# Atomic_clock_test_board_v1_1.net
KiCad netlist of a schematic drawn in EAGLE
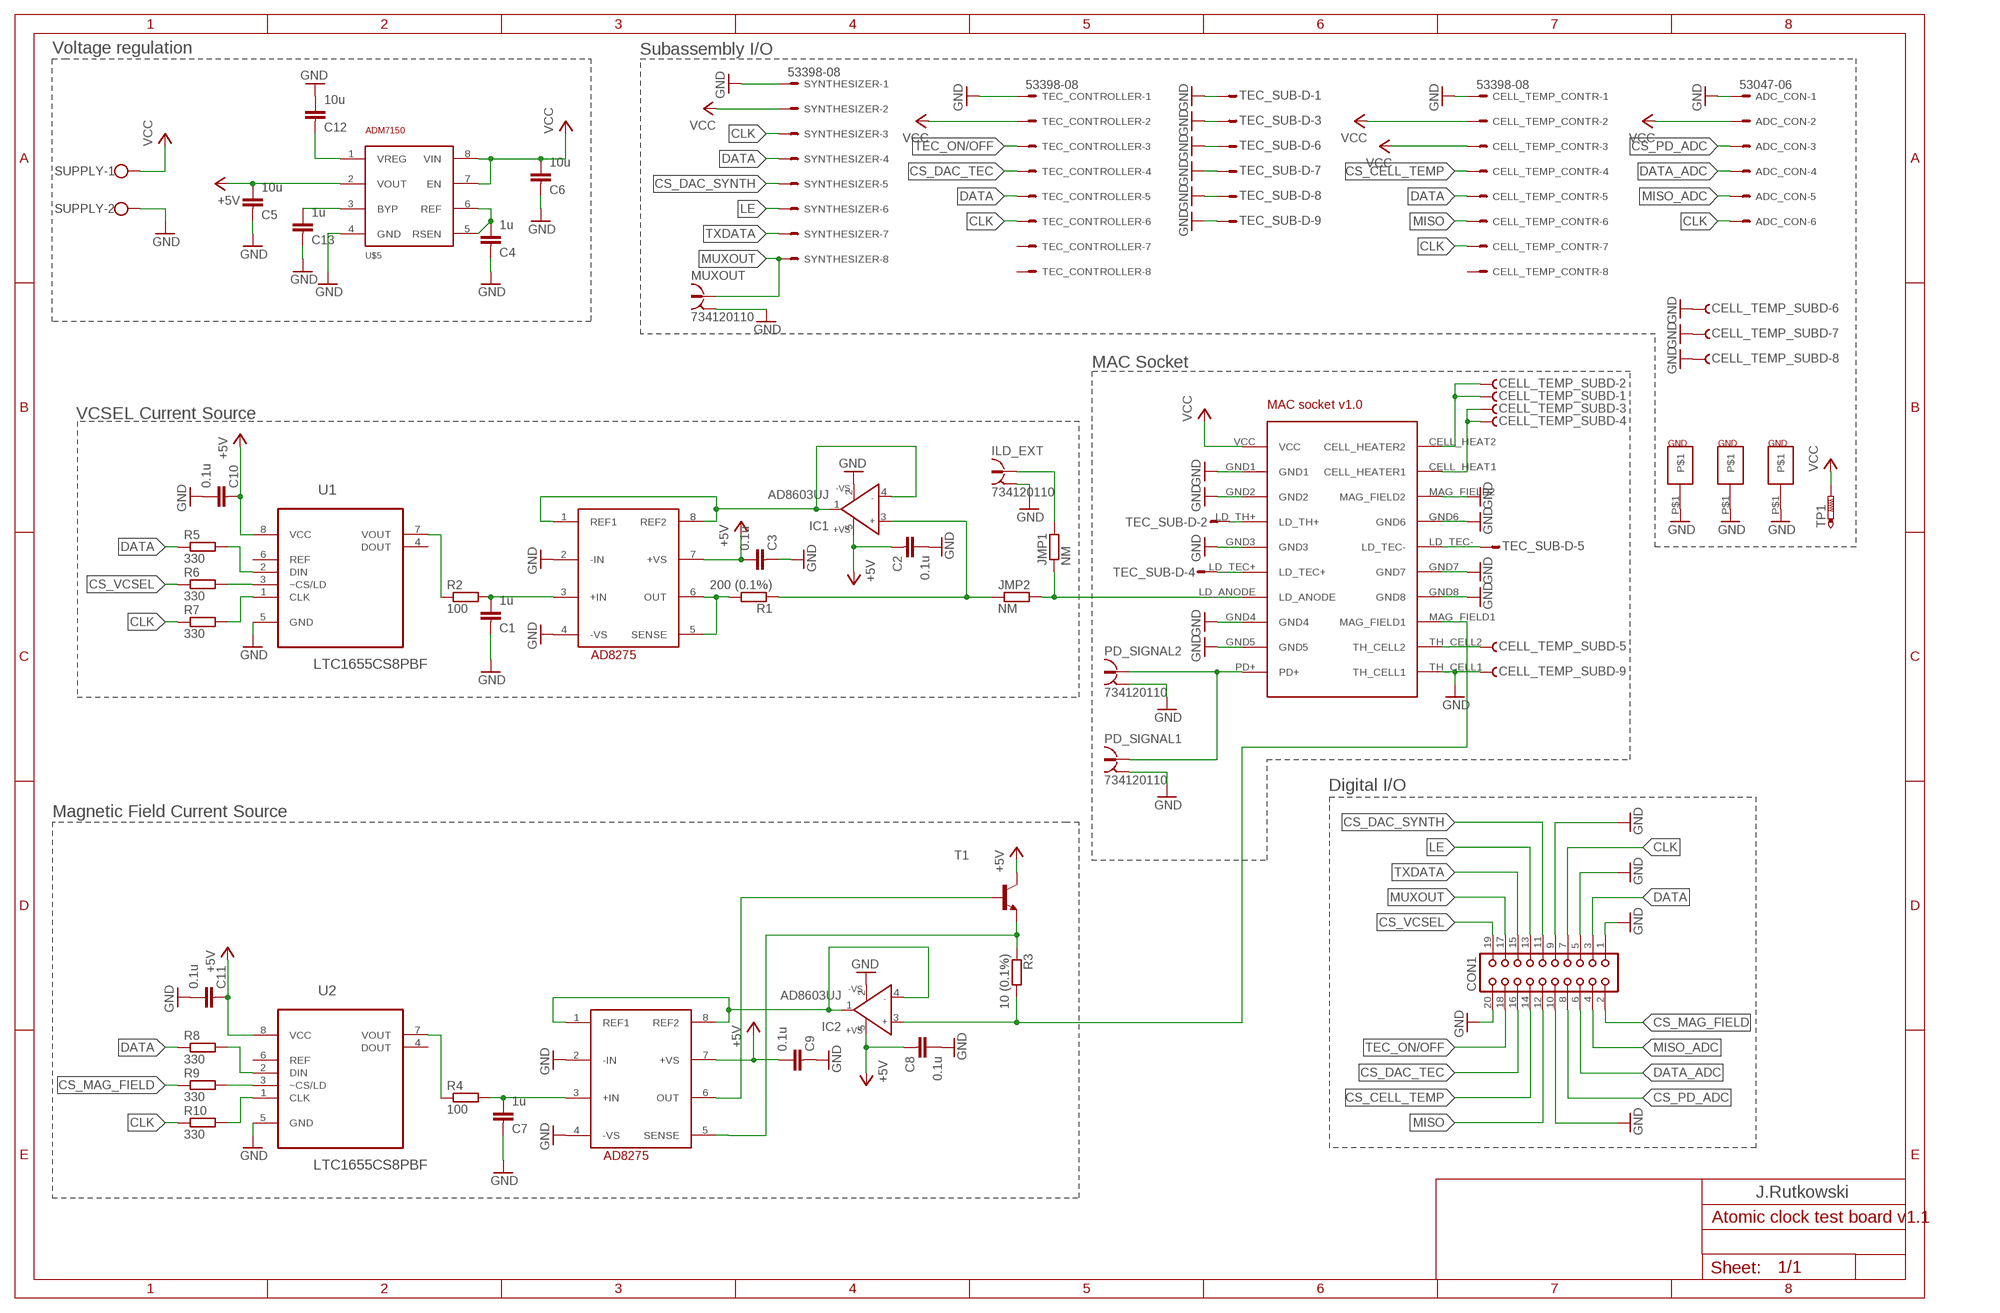
[diagram p0: schematic, sheet 1]

(export (version "E")
  (design (tool "Eeschema 10.0.6"))
  (components
    (comp (ref "ADC_CON")
      (value "53047-06")
      (footprint "eagle-import:53047-06")
      (fields (field (name "MPN") "53047-0610-C"))
      (libsource (lib "eagle-import") (part "53?-06047"))
    )
    (comp (ref "C1")
      (value "1u")
      (footprint "eagle-import:C0603K")
      (libsource (lib "eagle-import") (part "C-EUC0603K"))
    )
    (comp (ref "C2")
      (value "0.1u")
      (footprint "eagle-import:C0603K")
      (libsource (lib "eagle-import") (part "C-EUC0603K"))
    )
    (comp (ref "C3")
      (value "0.1u")
      (footprint "eagle-import:C0603K")
      (libsource (lib "eagle-import") (part "C-EUC0603K"))
    )
    (comp (ref "C4")
      (value "1u")
      (footprint "eagle-import:C0603K")
      (libsource (lib "eagle-import") (part "C-EUC0603K"))
    )
    (comp (ref "C5")
      (value "10u")
      (footprint "eagle-import:C0603K")
      (libsource (lib "eagle-import") (part "C-EUC0603K"))
    )
    (comp (ref "C6")
      (value "10u")
      (footprint "eagle-import:C0603K")
      (libsource (lib "eagle-import") (part "C-EUC0603K"))
    )
    (comp (ref "C7")
      (value "1u")
      (footprint "eagle-import:C0603K")
      (libsource (lib "eagle-import") (part "C-EUC0603K"))
    )
    (comp (ref "C8")
      (value "0.1u")
      (footprint "eagle-import:C0603K")
      (libsource (lib "eagle-import") (part "C-EUC0603K"))
    )
    (comp (ref "C9")
      (value "0.1u")
      (footprint "eagle-import:C0603K")
      (libsource (lib "eagle-import") (part "C-EUC0603K"))
    )
    (comp (ref "C10")
      (value "0.1u")
      (footprint "eagle-import:C0603K")
      (libsource (lib "eagle-import") (part "C-EUC0603K"))
    )
    (comp (ref "C11")
      (value "0.1u")
      (footprint "eagle-import:C0603K")
      (libsource (lib "eagle-import") (part "C-EUC0603K"))
    )
    (comp (ref "C12")
      (value "10u")
      (footprint "eagle-import:C0603K")
      (libsource (lib "eagle-import") (part "C-EUC0603K"))
    )
    (comp (ref "C13")
      (value "1u")
      (footprint "eagle-import:C0603K")
      (libsource (lib "eagle-import") (part "C-EUC0603K"))
    )
    (comp (ref "CELL_TEMP_CONTR")
      (value "53398-08")
      (footprint "eagle-import:53398-08")
      (libsource (lib "eagle-import") (part "53?-08398"))
    )
    (comp (ref "CELL_TEMP_SUBD")
      (value "F09HPS")
      (footprint "eagle-import:F09HP")
      (libsource (lib "eagle-import") (part "F09?SHP"))
    )
    (comp (ref "CON1")
      (value "CON20")
      (footprint "eagle-import:CON20")
      (libsource (lib "eagle-import") (part "CON20"))
    )
    (comp (ref "IC1")
      (value "AD8603UJ")
      (footprint "eagle-import:SOT23-5")
      (fields (field (name "MF") "ALTERA CORPORATION") (field (name "MPN") "AD8603AUJZ-REEL7"))
      (libsource (lib "eagle-import") (part "AD8603UJ"))
    )
    (comp (ref "IC2")
      (value "AD8603UJ")
      (footprint "eagle-import:SOT23-5")
      (fields (field (name "MF") "ALTERA CORPORATION") (field (name "MPN") "AD8603AUJZ-REEL7"))
      (libsource (lib "eagle-import") (part "AD8603UJ"))
    )
    (comp (ref "ILD_EXT")
      (value "734120110")
      (footprint "eagle-import:734120110")
      (libsource (lib "eagle-import") (part "734120110"))
    )
    (comp (ref "JMP1")
      (value "NM")
      (footprint "eagle-import:R0402")
      (libsource (lib "eagle-import") (part "R-EU_R0402"))
    )
    (comp (ref "JMP2")
      (value "NM")
      (footprint "eagle-import:R0402")
      (libsource (lib "eagle-import") (part "R-EU_R0402"))
    )
    (comp (ref "MUXOUT")
      (value "734120110")
      (footprint "eagle-import:734120110")
      (libsource (lib "eagle-import") (part "734120110"))
    )
    (comp (ref "PD_SIGNAL1")
      (value "734120110")
      (footprint "eagle-import:734120110")
      (libsource (lib "eagle-import") (part "734120110"))
    )
    (comp (ref "PD_SIGNAL2")
      (value "734120110")
      (footprint "eagle-import:734120110")
      (libsource (lib "eagle-import") (part "734120110"))
    )
    (comp (ref "R1")
      (value "200 (0.1%)")
      (footprint "eagle-import:R0603")
      (libsource (lib "eagle-import") (part "R-EU_R0603"))
    )
    (comp (ref "R2")
      (value "100")
      (footprint "eagle-import:R0603")
      (libsource (lib "eagle-import") (part "R-EU_R0603"))
    )
    (comp (ref "R3")
      (value "10 (0.1%)")
      (footprint "eagle-import:R0603")
      (libsource (lib "eagle-import") (part "R-EU_R0603"))
    )
    (comp (ref "R4")
      (value "100")
      (footprint "eagle-import:R0603")
      (libsource (lib "eagle-import") (part "R-EU_R0603"))
    )
    (comp (ref "R5")
      (value "330")
      (footprint "eagle-import:R0603")
      (libsource (lib "eagle-import") (part "R-EU_R0603"))
    )
    (comp (ref "R6")
      (value "330")
      (footprint "eagle-import:R0603")
      (libsource (lib "eagle-import") (part "R-EU_R0603"))
    )
    (comp (ref "R7")
      (value "330")
      (footprint "eagle-import:R0603")
      (libsource (lib "eagle-import") (part "R-EU_R0603"))
    )
    (comp (ref "R8")
      (value "330")
      (footprint "eagle-import:R0603")
      (libsource (lib "eagle-import") (part "R-EU_R0603"))
    )
    (comp (ref "R9")
      (value "330")
      (footprint "eagle-import:R0603")
      (libsource (lib "eagle-import") (part "R-EU_R0603"))
    )
    (comp (ref "R10")
      (value "330")
      (footprint "eagle-import:R0603")
      (libsource (lib "eagle-import") (part "R-EU_R0603"))
    )
    (comp (ref "SUPPLY")
      (value "W237-102")
      (footprint "eagle-import:W237-102")
      (fields (field (name "MPN") "237-102"))
      (libsource (lib "eagle-import") (part "W237-102"))
    )
    (comp (ref "SYNTHESIZER")
      (value "53398-08")
      (footprint "eagle-import:53398-08")
      (libsource (lib "eagle-import") (part "53?-08398"))
    )
    (comp (ref "T1")
      (value "MMBT3904LT1-NPN-SOT23-BEC")
      (footprint "eagle-import:SOT23-BEC")
      (libsource (lib "eagle-import") (part "-NPN-SOT23-BECMMBT3904LT1"))
    )
    (comp (ref "TEC_CONTROLLER")
      (value "53398-08")
      (footprint "eagle-import:53398-08")
      (libsource (lib "eagle-import") (part "53?-08398"))
    )
    (comp (ref "TEC_SUB-D")
      (value "M09HPS")
      (footprint "eagle-import:M09HP")
      (libsource (lib "eagle-import") (part "M09?SHP"))
    )
    (comp (ref "TP1")
      (value "PTR1PAD1-13")
      (footprint "eagle-import:P1-13")
      (libsource (lib "eagle-import") (part "PTR1PAD1-13"))
    )
    (comp (ref "U$1")
      (value "MAC_MOUNT_V1")
      (footprint "eagle-import:MAC_MOUNT_PAC_V1")
      (libsource (lib "eagle-import") (part "MAC_MOUNT_V1"))
    )
    (comp (ref "U$2")
      (value "AD8275")
      (footprint "eagle-import:MSOP08")
      (libsource (lib "eagle-import") (part "AD8275"))
    )
    (comp (ref "U$4")
      (value "AD8275")
      (footprint "eagle-import:MSOP08")
      (libsource (lib "eagle-import") (part "AD8275"))
    )
    (comp (ref "U$5")
      (value "ADM7150")
      (footprint "eagle-import:SO8")
      (libsource (lib "eagle-import") (part "ADM7150"))
    )
    (comp (ref "U$6")
      (value "GND_PAD")
      (footprint "eagle-import:GND_PAD")
      (libsource (lib "eagle-import") (part "GND_PAD"))
    )
    (comp (ref "U$7")
      (value "GND_PAD")
      (footprint "eagle-import:GND_PAD")
      (libsource (lib "eagle-import") (part "GND_PAD"))
    )
    (comp (ref "U$8")
      (value "GND_PAD")
      (footprint "eagle-import:GND_PAD")
      (libsource (lib "eagle-import") (part "GND_PAD"))
    )
    (comp (ref "U1")
      (value "LTC1655CS8PBF")
      (footprint "eagle-import:SOIC127P600X175-8N")
      (fields (field (name "MPN") "LTC1655CS8#PBF"))
      (libsource (lib "eagle-import") (part "LTC1655CS8PBF"))
    )
    (comp (ref "U2")
      (value "LTC1655CS8PBF")
      (footprint "eagle-import:SOIC127P600X175-8N")
      (fields (field (name "MPN") "LTC1655CS8#PBF"))
      (libsource (lib "eagle-import") (part "LTC1655CS8PBF"))
    )
  )
  (nets
    (net (code "1") (name "+5V") (class "Default")
      (node (ref "C10") (pin "2") (pinfunction "2_2") (pintype "passive"))
      (node (ref "C11") (pin "2") (pinfunction "2_2") (pintype "passive"))
      (node (ref "C2") (pin "2") (pinfunction "2_2") (pintype "passive"))
      (node (ref "C3") (pin "1") (pinfunction "1_1") (pintype "passive"))
      (node (ref "C5") (pin "1") (pinfunction "1_1") (pintype "passive"))
      (node (ref "C8") (pin "2") (pinfunction "2_2") (pintype "passive"))
      (node (ref "C9") (pin "1") (pinfunction "1_1") (pintype "passive"))
      (node (ref "IC1") (pin "5") (pinfunction "+VS_5") (pintype "input"))
      (node (ref "IC2") (pin "5") (pinfunction "+VS_5") (pintype "input"))
      (node (ref "T1") (pin "C") (pinfunction "C_C") (pintype "passive"))
      (node (ref "U$2") (pin "7") (pinfunction "+VS_7") (pintype "bidirectional"))
      (node (ref "U$4") (pin "7") (pinfunction "+VS_7") (pintype "bidirectional"))
      (node (ref "U$5") (pin "2") (pinfunction "VOUT_2") (pintype "bidirectional"))
      (node (ref "U1") (pin "8") (pinfunction "VCC_8") (pintype "power_in"))
      (node (ref "U2") (pin "8") (pinfunction "VCC_8") (pintype "power_in"))
    )
    (net (code "2") (name "CLK") (class "Default")
      (node (ref "ADC_CON") (pin "6") (pinfunction "S_6") (pintype "passive"))
      (node (ref "CELL_TEMP_CONTR") (pin "7") (pinfunction "S_7") (pintype "passive"))
      (node (ref "CON1") (pin "7") (pinfunction "7_7") (pintype "passive"))
      (node (ref "R10") (pin "1") (pinfunction "1_1") (pintype "passive"))
      (node (ref "R7") (pin "1") (pinfunction "1_1") (pintype "passive"))
      (node (ref "SYNTHESIZER") (pin "3") (pinfunction "S_3") (pintype "passive"))
      (node (ref "TEC_CONTROLLER") (pin "6") (pinfunction "S_6") (pintype "passive"))
    )
    (net (code "3") (name "CS_CELL_TEMP") (class "Default")
      (node (ref "CELL_TEMP_CONTR") (pin "4") (pinfunction "S_4") (pintype "passive"))
      (node (ref "CON1") (pin "14") (pinfunction "14_14") (pintype "passive"))
    )
    (net (code "4") (name "CS_DAC_SYNTH") (class "Default")
      (node (ref "CON1") (pin "11") (pinfunction "11_11") (pintype "passive"))
      (node (ref "SYNTHESIZER") (pin "5") (pinfunction "S_5") (pintype "passive"))
    )
    (net (code "5") (name "CS_DAC_TEC") (class "Default")
      (node (ref "CON1") (pin "16") (pinfunction "16_16") (pintype "passive"))
      (node (ref "TEC_CONTROLLER") (pin "4") (pinfunction "S_4") (pintype "passive"))
    )
    (net (code "6") (name "CS_MAG_FIELD") (class "Default")
      (node (ref "CON1") (pin "2") (pinfunction "2_2") (pintype "passive"))
      (node (ref "R9") (pin "1") (pinfunction "1_1") (pintype "passive"))
    )
    (net (code "7") (name "CS_PD_ADC") (class "Default")
      (node (ref "ADC_CON") (pin "3") (pinfunction "S_3") (pintype "passive"))
      (node (ref "CON1") (pin "8") (pinfunction "8_8") (pintype "passive"))
    )
    (net (code "8") (name "CS_VCSEL") (class "Default")
      (node (ref "CON1") (pin "19") (pinfunction "19_19") (pintype "passive"))
      (node (ref "R6") (pin "1") (pinfunction "1_1") (pintype "passive"))
    )
    (net (code "9") (name "DATA") (class "Default")
      (node (ref "CELL_TEMP_CONTR") (pin "5") (pinfunction "S_5") (pintype "passive"))
      (node (ref "CON1") (pin "3") (pinfunction "3_3") (pintype "passive"))
      (node (ref "R5") (pin "1") (pinfunction "1_1") (pintype "passive"))
      (node (ref "R8") (pin "1") (pinfunction "1_1") (pintype "passive"))
      (node (ref "SYNTHESIZER") (pin "4") (pinfunction "S_4") (pintype "passive"))
      (node (ref "TEC_CONTROLLER") (pin "5") (pinfunction "S_5") (pintype "passive"))
    )
    (net (code "10") (name "DATA_ADC") (class "Default")
      (node (ref "ADC_CON") (pin "4") (pinfunction "S_4") (pintype "passive"))
      (node (ref "CON1") (pin "6") (pinfunction "6_6") (pintype "passive"))
    )
    (net (code "11") (name "GND") (class "Default")
      (node (ref "ADC_CON") (pin "1") (pinfunction "S_1") (pintype "passive"))
      (node (ref "C1") (pin "2") (pinfunction "2_2") (pintype "passive"))
      (node (ref "C10") (pin "1") (pinfunction "1_1") (pintype "passive"))
      (node (ref "C11") (pin "1") (pinfunction "1_1") (pintype "passive"))
      (node (ref "C12") (pin "1") (pinfunction "1_1") (pintype "passive"))
      (node (ref "C13") (pin "2") (pinfunction "2_2") (pintype "passive"))
      (node (ref "C2") (pin "1") (pinfunction "1_1") (pintype "passive"))
      (node (ref "C3") (pin "2") (pinfunction "2_2") (pintype "passive"))
      (node (ref "C4") (pin "2") (pinfunction "2_2") (pintype "passive"))
      (node (ref "C5") (pin "2") (pinfunction "2_2") (pintype "passive"))
      (node (ref "C6") (pin "2") (pinfunction "2_2") (pintype "passive"))
      (node (ref "C7") (pin "2") (pinfunction "2_2") (pintype "passive"))
      (node (ref "C8") (pin "1") (pinfunction "1_1") (pintype "passive"))
      (node (ref "C9") (pin "2") (pinfunction "2_2") (pintype "passive"))
      (node (ref "CELL_TEMP_CONTR") (pin "1") (pinfunction "S_1") (pintype "passive"))
      (node (ref "CELL_TEMP_SUBD") (pin "6") (pinfunction "F_6") (pintype "passive"))
      (node (ref "CELL_TEMP_SUBD") (pin "7") (pinfunction "F_7") (pintype "passive"))
      (node (ref "CELL_TEMP_SUBD") (pin "8") (pinfunction "F_8") (pintype "passive"))
      (node (ref "CELL_TEMP_SUBD") (pin "9") (pinfunction "F_9") (pintype "passive"))
      (node (ref "CON1") (pin "1") (pinfunction "1_1") (pintype "passive"))
      (node (ref "CON1") (pin "10") (pinfunction "10_10") (pintype "passive"))
      (node (ref "CON1") (pin "20") (pinfunction "20_20") (pintype "passive"))
      (node (ref "CON1") (pin "5") (pinfunction "5_5") (pintype "passive"))
      (node (ref "CON1") (pin "9") (pinfunction "9_9") (pintype "passive"))
      (node (ref "IC1") (pin "2") (pinfunction "-VS_2") (pintype "input"))
      (node (ref "IC2") (pin "2") (pinfunction "-VS_2") (pintype "input"))
      (node (ref "ILD_EXT") (pin "S@1") (pinfunction "2_S@1") (pintype "passive"))
      (node (ref "ILD_EXT") (pin "S@2") (pinfunction "2_S@2") (pintype "passive"))
      (node (ref "ILD_EXT") (pin "S@3") (pinfunction "2_S@3") (pintype "passive"))
      (node (ref "MUXOUT") (pin "S@1") (pinfunction "2_S@1") (pintype "passive"))
      (node (ref "MUXOUT") (pin "S@2") (pinfunction "2_S@2") (pintype "passive"))
      (node (ref "MUXOUT") (pin "S@3") (pinfunction "2_S@3") (pintype "passive"))
      (node (ref "PD_SIGNAL1") (pin "S@1") (pinfunction "2_S@1") (pintype "passive"))
      (node (ref "PD_SIGNAL1") (pin "S@2") (pinfunction "2_S@2") (pintype "passive"))
      (node (ref "PD_SIGNAL1") (pin "S@3") (pinfunction "2_S@3") (pintype "passive"))
      (node (ref "PD_SIGNAL2") (pin "S@1") (pinfunction "2_S@1") (pintype "passive"))
      (node (ref "PD_SIGNAL2") (pin "S@2") (pinfunction "2_S@2") (pintype "passive"))
      (node (ref "PD_SIGNAL2") (pin "S@3") (pinfunction "2_S@3") (pintype "passive"))
      (node (ref "SUPPLY") (pin "2") (pinfunction "KL_2") (pintype "passive"))
      (node (ref "SYNTHESIZER") (pin "1") (pinfunction "S_1") (pintype "passive"))
      (node (ref "TEC_CONTROLLER") (pin "1") (pinfunction "S_1") (pintype "passive"))
      (node (ref "TEC_SUB-D") (pin "1") (pinfunction "M_1") (pintype "passive"))
      (node (ref "TEC_SUB-D") (pin "3") (pinfunction "M_3") (pintype "passive"))
      (node (ref "TEC_SUB-D") (pin "6") (pinfunction "M_6") (pintype "passive"))
      (node (ref "TEC_SUB-D") (pin "7") (pinfunction "M_7") (pintype "passive"))
      (node (ref "TEC_SUB-D") (pin "8") (pinfunction "M_8") (pintype "passive"))
      (node (ref "TEC_SUB-D") (pin "9") (pinfunction "M_9") (pintype "passive"))
      (node (ref "U$1") (pin "GND1") (pinfunction "GND1_GND1") (pintype "bidirectional"))
      (node (ref "U$1") (pin "GND2") (pinfunction "GND2_GND2") (pintype "bidirectional"))
      (node (ref "U$1") (pin "GND3") (pinfunction "GND3_GND3") (pintype "bidirectional"))
      (node (ref "U$1") (pin "GND4") (pinfunction "GND4_GND4") (pintype "bidirectional"))
      (node (ref "U$1") (pin "GND5") (pinfunction "GND5_GND5") (pintype "bidirectional"))
      (node (ref "U$1") (pin "GND6") (pinfunction "GND6_GND6") (pintype "bidirectional"))
      (node (ref "U$1") (pin "GND7") (pinfunction "GND7_GND7") (pintype "bidirectional"))
      (node (ref "U$1") (pin "GND8") (pinfunction "GND8_GND8") (pintype "bidirectional"))
      (node (ref "U$1") (pin "MAG_FIELD2") (pinfunction "MAG_FIELD2_MAG_FIELD2") (pintype "bidirectional"))
      (node (ref "U$1") (pin "TH_CELL1") (pinfunction "TH_CELL1_TH_CELL1") (pintype "bidirectional"))
      (node (ref "U$2") (pin "2") (pinfunction "-IN_2") (pintype "bidirectional"))
      (node (ref "U$2") (pin "4") (pinfunction "-VS_4") (pintype "bidirectional"))
      (node (ref "U$4") (pin "2") (pinfunction "-IN_2") (pintype "bidirectional"))
      (node (ref "U$4") (pin "4") (pinfunction "-VS_4") (pintype "bidirectional"))
      (node (ref "U$5") (pin "4") (pinfunction "GND_4") (pintype "bidirectional"))
      (node (ref "U$6") (pin "P$1") (pinfunction "P$1_P$1") (pintype "bidirectional"))
      (node (ref "U$7") (pin "P$1") (pinfunction "P$1_P$1") (pintype "bidirectional"))
      (node (ref "U$8") (pin "P$1") (pinfunction "P$1_P$1") (pintype "bidirectional"))
      (node (ref "U1") (pin "5") (pinfunction "GND_5") (pintype "passive"))
      (node (ref "U2") (pin "5") (pinfunction "GND_5") (pintype "passive"))
    )
    (net (code "12") (name "LE") (class "Default")
      (node (ref "CON1") (pin "13") (pinfunction "13_13") (pintype "passive"))
      (node (ref "SYNTHESIZER") (pin "6") (pinfunction "S_6") (pintype "passive"))
    )
    (net (code "13") (name "MISO") (class "Default")
      (node (ref "CELL_TEMP_CONTR") (pin "6") (pinfunction "S_6") (pintype "passive"))
      (node (ref "CON1") (pin "12") (pinfunction "12_12") (pintype "passive"))
    )
    (net (code "14") (name "MISO_ADC") (class "Default")
      (node (ref "ADC_CON") (pin "5") (pinfunction "S_5") (pintype "passive"))
      (node (ref "CON1") (pin "4") (pinfunction "4_4") (pintype "passive"))
    )
    (net (code "15") (name "MUXOUT") (class "Default")
      (node (ref "CON1") (pin "17") (pinfunction "17_17") (pintype "passive"))
      (node (ref "MUXOUT") (pin "1") (pinfunction "1_1") (pintype "passive"))
      (node (ref "SYNTHESIZER") (pin "8") (pinfunction "S_8") (pintype "passive"))
    )
    (net (code "16") (name "Net-(CELL_TEMP_SUBDA-F)") (class "Default")
      (node (ref "CELL_TEMP_SUBD") (pin "1") (pinfunction "F_1") (pintype "passive"))
      (node (ref "CELL_TEMP_SUBD") (pin "2") (pinfunction "F_2") (pintype "passive"))
      (node (ref "U$1") (pin "CELL_HEAT2") (pinfunction "CELL_HEATER2_CELL_HEAT2") (pintype "bidirectional"))
    )
    (net (code "17") (name "Net-(CELL_TEMP_SUBDC-F)") (class "Default")
      (node (ref "CELL_TEMP_SUBD") (pin "3") (pinfunction "F_3") (pintype "passive"))
      (node (ref "CELL_TEMP_SUBD") (pin "4") (pinfunction "F_4") (pintype "passive"))
      (node (ref "U$1") (pin "CELL_HEAT1") (pinfunction "CELL_HEATER1_CELL_HEAT1") (pintype "bidirectional"))
    )
    (net (code "18") (name "Net-(CELL_TEMP_SUBDE-F)") (class "Default")
      (node (ref "CELL_TEMP_SUBD") (pin "5") (pinfunction "F_5") (pintype "passive"))
      (node (ref "U$1") (pin "TH_CELL2") (pinfunction "TH_CELL2_TH_CELL2") (pintype "bidirectional"))
    )
    (net (code "19") (name "Net-(IC1-IN+)") (class "Default")
      (node (ref "IC1") (pin "3") (pinfunction "IN+_3") (pintype "input"))
      (node (ref "JMP2") (pin "1") (pinfunction "1_1") (pintype "passive"))
      (node (ref "R1") (pin "1") (pinfunction "1_1") (pintype "passive"))
    )
    (net (code "20") (name "Net-(IC1-IN-)") (class "Default")
      (node (ref "IC1") (pin "1") (pinfunction "OUT_1") (pintype "output"))
      (node (ref "IC1") (pin "4") (pinfunction "IN-_4") (pintype "input"))
      (node (ref "U$2") (pin "1") (pinfunction "REF1_1") (pintype "bidirectional"))
      (node (ref "U$2") (pin "8") (pinfunction "REF2_8") (pintype "bidirectional"))
    )
    (net (code "21") (name "Net-(IC2-IN+)") (class "Default")
      (node (ref "IC2") (pin "3") (pinfunction "IN+_3") (pintype "input"))
      (node (ref "R3") (pin "2") (pinfunction "2_2") (pintype "passive"))
      (node (ref "U$1") (pin "MAG_FIELD1") (pinfunction "MAG_FIELD1_MAG_FIELD1") (pintype "bidirectional"))
    )
    (net (code "22") (name "Net-(IC2-IN-)") (class "Default")
      (node (ref "IC2") (pin "1") (pinfunction "OUT_1") (pintype "output"))
      (node (ref "IC2") (pin "4") (pinfunction "IN-_4") (pintype "input"))
      (node (ref "U$4") (pin "1") (pinfunction "REF1_1") (pintype "bidirectional"))
      (node (ref "U$4") (pin "8") (pinfunction "REF2_8") (pintype "bidirectional"))
    )
    (net (code "23") (name "Net-(ILD_EXT-Pad1)") (class "Default")
      (node (ref "ILD_EXT") (pin "1") (pinfunction "1_1") (pintype "passive"))
      (node (ref "JMP1") (pin "2") (pinfunction "2_2") (pintype "passive"))
    )
    (net (code "24") (name "Net-(JMP1-Pad1)") (class "Default")
      (node (ref "JMP1") (pin "1") (pinfunction "1_1") (pintype "passive"))
      (node (ref "JMP2") (pin "2") (pinfunction "2_2") (pintype "passive"))
      (node (ref "U$1") (pin "LD_ANODE") (pinfunction "LD_ANODE_LD_ANODE") (pintype "bidirectional"))
    )
    (net (code "25") (name "Net-(PD_SIGNAL1-Pad1)") (class "Default")
      (node (ref "PD_SIGNAL1") (pin "1") (pinfunction "1_1") (pintype "passive"))
      (node (ref "PD_SIGNAL2") (pin "1") (pinfunction "1_1") (pintype "passive"))
      (node (ref "U$1") (pin "PD+") (pinfunction "PD+_PD+") (pintype "bidirectional"))
    )
    (net (code "26") (name "Net-(TEC_SUB-DB-M)") (class "Default")
      (node (ref "TEC_SUB-D") (pin "2") (pinfunction "M_2") (pintype "passive"))
      (node (ref "U$1") (pin "LD_TH+") (pinfunction "LD_TH+_LD_TH+") (pintype "bidirectional"))
    )
    (net (code "27") (name "Net-(TEC_SUB-DD-M)") (class "Default")
      (node (ref "TEC_SUB-D") (pin "4") (pinfunction "M_4") (pintype "passive"))
      (node (ref "U$1") (pin "LD_TEC+") (pinfunction "LD_TEC+_LD_TEC+") (pintype "bidirectional"))
    )
    (net (code "28") (name "Net-(TEC_SUB-DE-M)") (class "Default")
      (node (ref "TEC_SUB-D") (pin "5") (pinfunction "M_5") (pintype "passive"))
      (node (ref "U$1") (pin "LD_TEC-") (pinfunction "LD_TEC-_LD_TEC-") (pintype "bidirectional"))
    )
    (net (code "29") (name "Net-(U$2-+IN)") (class "Default")
      (node (ref "C1") (pin "1") (pinfunction "1_1") (pintype "passive"))
      (node (ref "R2") (pin "2") (pinfunction "2_2") (pintype "passive"))
      (node (ref "U$2") (pin "3") (pinfunction "+IN_3") (pintype "bidirectional"))
    )
    (net (code "30") (name "Net-(U$2-OUT)") (class "Default")
      (node (ref "R1") (pin "2") (pinfunction "2_2") (pintype "passive"))
      (node (ref "U$2") (pin "5") (pinfunction "SENSE_5") (pintype "bidirectional"))
      (node (ref "U$2") (pin "6") (pinfunction "OUT_6") (pintype "bidirectional"))
    )
    (net (code "31") (name "Net-(U$4-+IN)") (class "Default")
      (node (ref "C7") (pin "1") (pinfunction "1_1") (pintype "passive"))
      (node (ref "R4") (pin "2") (pinfunction "2_2") (pintype "passive"))
      (node (ref "U$4") (pin "3") (pinfunction "+IN_3") (pintype "bidirectional"))
    )
    (net (code "32") (name "Net-(U$4-OUT)") (class "Default")
      (node (ref "T1") (pin "B") (pinfunction "B_B") (pintype "passive"))
      (node (ref "U$4") (pin "6") (pinfunction "OUT_6") (pintype "bidirectional"))
    )
    (net (code "33") (name "Net-(U$4-SENSE)") (class "Default")
      (node (ref "R3") (pin "1") (pinfunction "1_1") (pintype "passive"))
      (node (ref "T1") (pin "E") (pinfunction "E_E") (pintype "passive"))
      (node (ref "U$4") (pin "5") (pinfunction "SENSE_5") (pintype "bidirectional"))
    )
    (net (code "34") (name "Net-(U$5-BYP)") (class "Default")
      (node (ref "C13") (pin "1") (pinfunction "1_1") (pintype "passive"))
      (node (ref "U$5") (pin "3") (pinfunction "BYP_3") (pintype "bidirectional"))
    )
    (net (code "35") (name "Net-(U$5-REF)") (class "Default")
      (node (ref "C4") (pin "1") (pinfunction "1_1") (pintype "passive"))
      (node (ref "U$5") (pin "5") (pinfunction "RSEN_5") (pintype "bidirectional"))
      (node (ref "U$5") (pin "6") (pinfunction "REF_6") (pintype "bidirectional"))
    )
    (net (code "36") (name "Net-(U$5-VREG)") (class "Default")
      (node (ref "C12") (pin "2") (pinfunction "2_2") (pintype "passive"))
      (node (ref "U$5") (pin "1") (pinfunction "VREG_1") (pintype "bidirectional"))
    )
    (net (code "37") (name "Net-(U1-CLK)") (class "Default")
      (node (ref "R7") (pin "2") (pinfunction "2_2") (pintype "passive"))
      (node (ref "U1") (pin "1") (pinfunction "CLK_1") (pintype "input"))
    )
    (net (code "38") (name "Net-(U1-DIN)") (class "Default")
      (node (ref "R5") (pin "2") (pinfunction "2_2") (pintype "passive"))
      (node (ref "U1") (pin "2") (pinfunction "DIN_2") (pintype "input"))
    )
    (net (code "39") (name "Net-(U1-VOUT)") (class "Default")
      (node (ref "R2") (pin "1") (pinfunction "1_1") (pintype "passive"))
      (node (ref "U1") (pin "7") (pinfunction "VOUT_7") (pintype "output"))
    )
    (net (code "40") (name "Net-(U1-~{CS{slash}LD})") (class "Default")
      (node (ref "R6") (pin "2") (pinfunction "2_2") (pintype "passive"))
      (node (ref "U1") (pin "3") (pinfunction "~{CS/LD}_3") (pintype "input"))
    )
    (net (code "41") (name "Net-(U2-CLK)") (class "Default")
      (node (ref "R10") (pin "2") (pinfunction "2_2") (pintype "passive"))
      (node (ref "U2") (pin "1") (pinfunction "CLK_1") (pintype "input"))
    )
    (net (code "42") (name "Net-(U2-DIN)") (class "Default")
      (node (ref "R8") (pin "2") (pinfunction "2_2") (pintype "passive"))
      (node (ref "U2") (pin "2") (pinfunction "DIN_2") (pintype "input"))
    )
    (net (code "43") (name "Net-(U2-VOUT)") (class "Default")
      (node (ref "R4") (pin "1") (pinfunction "1_1") (pintype "passive"))
      (node (ref "U2") (pin "7") (pinfunction "VOUT_7") (pintype "output"))
    )
    (net (code "44") (name "Net-(U2-~{CS{slash}LD})") (class "Default")
      (node (ref "R9") (pin "2") (pinfunction "2_2") (pintype "passive"))
      (node (ref "U2") (pin "3") (pinfunction "~{CS/LD}_3") (pintype "input"))
    )
    (net (code "45") (name "TEC_ON{slash}OFF") (class "Default")
      (node (ref "CON1") (pin "18") (pinfunction "18_18") (pintype "passive"))
      (node (ref "TEC_CONTROLLER") (pin "3") (pinfunction "S_3") (pintype "passive"))
    )
    (net (code "46") (name "TXDATA") (class "Default")
      (node (ref "CON1") (pin "15") (pinfunction "15_15") (pintype "passive"))
      (node (ref "SYNTHESIZER") (pin "7") (pinfunction "S_7") (pintype "passive"))
    )
    (net (code "47") (name "VCC") (class "Default")
      (node (ref "ADC_CON") (pin "2") (pinfunction "S_2") (pintype "passive"))
      (node (ref "C6") (pin "1") (pinfunction "1_1") (pintype "passive"))
      (node (ref "CELL_TEMP_CONTR") (pin "2") (pinfunction "S_2") (pintype "passive"))
      (node (ref "CELL_TEMP_CONTR") (pin "3") (pinfunction "S_3") (pintype "passive"))
      (node (ref "SUPPLY") (pin "1") (pinfunction "KL_1") (pintype "passive"))
      (node (ref "SYNTHESIZER") (pin "2") (pinfunction "S_2") (pintype "passive"))
      (node (ref "TEC_CONTROLLER") (pin "2") (pinfunction "S_2") (pintype "passive"))
      (node (ref "TP1") (pin "TP") (pinfunction "TP_TP") (pintype "input"))
      (node (ref "U$1") (pin "VCC") (pinfunction "VCC_VCC") (pintype "bidirectional"))
      (node (ref "U$5") (pin "7") (pinfunction "EN_7") (pintype "bidirectional"))
      (node (ref "U$5") (pin "8") (pinfunction "VIN_8") (pintype "bidirectional"))
    )
    (net (code "48") (name "unconnected-(CELL_TEMP_CONTRH-S-Pad8)") (class "Default")
      (node (ref "CELL_TEMP_CONTR") (pin "8") (pinfunction "S_8") (pintype "passive"))
    )
    (net (code "49") (name "unconnected-(TEC_CONTROLLERG-S-Pad7)") (class "Default")
      (node (ref "TEC_CONTROLLER") (pin "7") (pinfunction "S_7") (pintype "passive"))
    )
    (net (code "50") (name "unconnected-(TEC_CONTROLLERH-S-Pad8)") (class "Default")
      (node (ref "TEC_CONTROLLER") (pin "8") (pinfunction "S_8") (pintype "passive"))
    )
    (net (code "51") (name "unconnected-(U1-DOUT-Pad4)") (class "Default")
      (node (ref "U1") (pin "4") (pinfunction "DOUT_4") (pintype "output"))
    )
    (net (code "52") (name "unconnected-(U1-REF-Pad6)") (class "Default")
      (node (ref "U1") (pin "6") (pinfunction "REF_6") (pintype "input"))
    )
    (net (code "53") (name "unconnected-(U2-DOUT-Pad4)") (class "Default")
      (node (ref "U2") (pin "4") (pinfunction "DOUT_4") (pintype "output"))
    )
    (net (code "54") (name "unconnected-(U2-REF-Pad6)") (class "Default")
      (node (ref "U2") (pin "6") (pinfunction "REF_6") (pintype "input"))
    )
  )
)
